# OBDII-Ist.net
KiCad netlist of a schematic drawn in Altium Designer
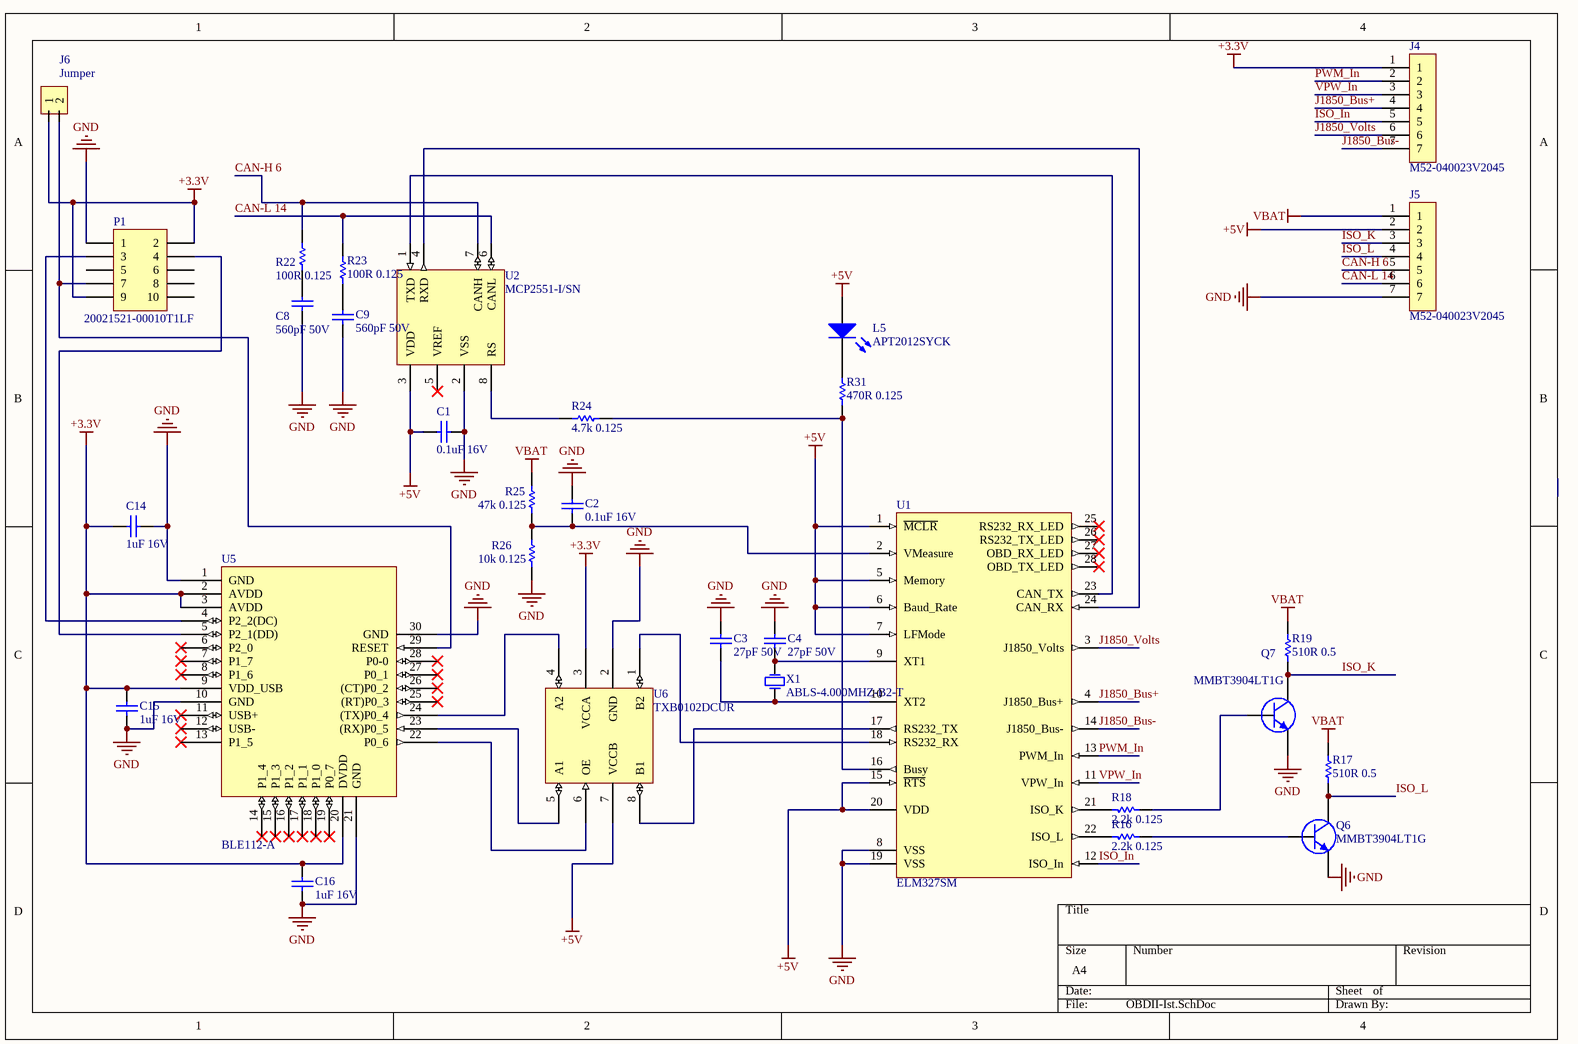
[diagram p0: OBDII-Ist.SchDoc]

(export (version "E")
  (design (tool "Eeschema 10.0.6"))
  (components
    (comp (ref "C1")
      (value "0.1uF 16V")
      (footprint "1608[0603]")
      (description "Surface-Mount Ceramic Multilayer Capacitor, 0.1uF, X5R, 10% Tolerance, 0603 Size, 16V")
      (fields (field (name "PUBLISHER") "Altium Limited"))
      (libsource (lib "OBDII-components") (part "GRM188R61C104KA01D"))
    )
    (comp (ref "C2")
      (value "0.1uF 16V")
      (footprint "1608[0603]")
      (description "Surface-Mount Ceramic Multilayer Capacitor, 0.1uF, X5R, 10% Tolerance, 0603 Size, 16V")
      (fields (field (name "PUBLISHER") "Altium Limited"))
      (libsource (lib "OBDII-components") (part "GRM188R61C104KA01D"))
    )
    (comp (ref "C3")
      (value "27pF 50V")
      (footprint "1608[0603]")
      (description "Surface-Mount Ceramic Multilayer Capacitor, 27pF, 5% Tolerance, 0603 Size, 50V")
      (fields (field (name "PUBLISHER") "Altium Limited"))
      (libsource (lib "OBDII-components") (part "CC0603JRNPO9BN270"))
    )
    (comp (ref "C4")
      (value "27pF 50V")
      (footprint "1608[0603]")
      (description "Surface-Mount Ceramic Multilayer Capacitor, 27pF, 5% Tolerance, 0603 Size, 50V")
      (fields (field (name "PUBLISHER") "Altium Limited"))
      (libsource (lib "OBDII-components") (part "CC0603JRNPO9BN270"))
    )
    (comp (ref "C8")
      (value "560pF 50V")
      (footprint "0402")
      (description "Surface-Mount Ceramic Multilayer Capacitor, 560pF, 5% Tolerance, 0402 Size, 50V")
      (fields (field (name "PUBLISHER") "Altium Limited"))
      (libsource (lib "OBDII-components") (part "C0402C561J5GACTU"))
    )
    (comp (ref "C9")
      (value "560pF 50V")
      (footprint "0402")
      (description "Surface-Mount Ceramic Multilayer Capacitor, 560pF, 5% Tolerance, 0402 Size, 50V")
      (fields (field (name "PUBLISHER") "Altium Limited"))
      (libsource (lib "OBDII-components") (part "C0402C561J5GACTU"))
    )
    (comp (ref "C14")
      (value "1uF 16V")
      (footprint "1608[0603]")
      (description "Surface-Mount Ceramic Multilayer Capacitor, 1uF, X7R, 10% Tolerance, 0603 Size, 16V")
      (libsource (lib "OBDII-components") (part "C1608X7R1C105K080AC"))
    )
    (comp (ref "C15")
      (value "1uF 16V")
      (footprint "1608[0603]")
      (description "Surface-Mount Ceramic Multilayer Capacitor, 1uF, X7R, 10% Tolerance, 0603 Size, 16V")
      (libsource (lib "OBDII-components") (part "C1608X7R1C105K080AC"))
    )
    (comp (ref "C16")
      (value "1uF 16V")
      (footprint "1608[0603]")
      (description "Surface-Mount Ceramic Multilayer Capacitor, 1uF, X7R, 10% Tolerance, 0603 Size, 16V")
      (libsource (lib "OBDII-components") (part "C1608X7R1C105K080AC"))
    )
    (comp (ref "J4")
      (value "M52-040023V2045")
      (footprint "M52-040023V2045_hols")
      (description "CONN HEADER .050\" 50POS PCB GOLD")
      (fields (field (name "MANUFACTURER") "Harwin"))
      (libsource (lib "OBDII-components") (part "M52-040023V2045_hols"))
    )
    (comp (ref "J5")
      (value "M52-040023V2045")
      (footprint "M52-040023V2045_hols")
      (description "CONN HEADER .050\" 50POS PCB GOLD")
      (fields (field (name "MANUFACTURER") "Harwin"))
      (libsource (lib "OBDII-components") (part "M52-040023V2045_hols"))
    )
    (comp (ref "J6")
      (value "Jumper")
      (footprint "Jumper")
      (description "Solder Jumper")
      (libsource (lib "OBDII-components") (part "Jumper"))
    )
    (comp (ref "L5")
      (value "APT2012SYCK")
      (footprint "LED-0805")
      (description "Typical BLUE SiC LED")
      (libsource (lib "OBDII-components") (part "APT2012SYCK"))
    )
    (comp (ref "P1")
      (value "20021521-00010T1LF")
      (footprint "20021521-00010T1LF")
      (description "Header, 5-Pin, Dual row,SMT SHOULDED")
      (fields (field (name "TYPE") "20021521-00010T1LF") (field (name "PUBLISHER") "Altium Limited"))
      (libsource (lib "OBDII-components") (part "20021521-00010T1LF"))
    )
    (comp (ref "Q6")
      (value "MMBT3904LT1G")
      (footprint "SOT23")
      (description "NPN 3904 General Purpose Amplifier")
      (fields
        (field (name "MANUFACTURER") "ON Semiconductor")
        (field (name "PUBLISHER") "Vanteon")
        (field (name "APPROVED") "Yes by Implemenation")
      )
      (libsource (lib "OBDII-components") (part "MMBT3904LT1G"))
    )
    (comp (ref "Q7")
      (value "MMBT3904LT1G")
      (footprint "SOT23")
      (description "NPN 3904 General Purpose Amplifier")
      (fields
        (field (name "MANUFACTURER") "ON Semiconductor")
        (field (name "PUBLISHER") "Vanteon")
        (field (name "APPROVED") "Yes by Implemenation")
      )
      (libsource (lib "OBDII-components") (part "MMBT3904LT1G"))
    )
    (comp (ref "R16")
      (value "2.2k 0.125")
      (footprint "ERA-0805")
      (description "Rectangular Thick Film Chip Resistor, 2.2 kOhm, 0.1% Tolerance, 0805 Size, 0.125 W")
      (libsource (lib "OBDII-components") (part "ERA-6AEB222V"))
    )
    (comp (ref "R17")
      (value "510R 0.5")
      (footprint "ERJ-1210")
      (description "Rectangular Thick Film Chip Resistor, 510 Ohm, 1% Tolerance, 1210 Size, 0.5 W")
      (libsource (lib "OBDII-components") (part "ERJ-14NF5100U"))
    )
    (comp (ref "R18")
      (value "2.2k 0.125")
      (footprint "ERA-0805")
      (description "Rectangular Thick Film Chip Resistor, 2.2 kOhm, 0.1% Tolerance, 0805 Size, 0.125 W")
      (libsource (lib "OBDII-components") (part "ERA-6AEB222V"))
    )
    (comp (ref "R19")
      (value "510R 0.5")
      (footprint "ERJ-1210")
      (description "Rectangular Thick Film Chip Resistor, 510 Ohm, 1% Tolerance, 1210 Size, 0.5 W")
      (libsource (lib "OBDII-components") (part "ERJ-14NF5100U"))
    )
    (comp (ref "R22")
      (value "100R 0.125")
      (footprint "ERA-0805")
      (description "Rectangular Thick Film Chip Resistor, 100 Ohm, 0.1% Tolerance, 0805 Size, 0.125 W")
      (libsource (lib "OBDII-components") (part "ERA-6AEB101V"))
    )
    (comp (ref "R23")
      (value "100R 0.125")
      (footprint "ERA-0805")
      (description "Rectangular Thick Film Chip Resistor, 100 Ohm, 0.1% Tolerance, 0805 Size, 0.125 W")
      (libsource (lib "OBDII-components") (part "ERA-6AEB101V"))
    )
    (comp (ref "R24")
      (value "4.7k 0.125")
      (footprint "ERA-0805")
      (description "Rectangular Thick Film Chip Resistor, 4.7 kOhm, 0.1% Tolerance, 0805 Size, 0.125 W")
      (libsource (lib "OBDII-components") (part "ERA-6AEB472V"))
    )
    (comp (ref "R25")
      (value "47k 0.125")
      (footprint "ERA-0805")
      (description "Rectangular Thick Film Chip Resistor, 47 kOhm, 0.1% Tolerance, 0805 Size, 0.125 W")
      (libsource (lib "OBDII-components") (part "ERA-6AEB473V"))
    )
    (comp (ref "R26")
      (value "10k 0.125")
      (footprint "ERA-0805")
      (description "Rectangular Thick Film Chip Resistor, 10 kOhm, 0.1% Tolerance, 0805 Size, 0.125 W")
      (libsource (lib "OBDII-components") (part "ERA-6AEB103V"))
    )
    (comp (ref "R31")
      (value "470R 0.125")
      (footprint "ERA-0805")
      (description "Rectangular Thick Film Chip Resistor, 470 Ohm, 0.1% Tolerance, 0805 Size, 0.125 W")
      (libsource (lib "OBDII-components") (part "ERA-6AEB471V"))
    )
    (comp (ref "U1")
      (value "ELM327SM")
      (footprint "SOIC-28N")
      (description "OBDII Interpreter IC")
      (fields (field (name "MANUFACTURER") "Elm Electronics"))
      (libsource (lib "OBDII-components") (part "ELM327_SOIC"))
    )
    (comp (ref "U2")
      (value "MCP2551-I/SN")
      (footprint "SOIC8N")
      (description "IC TRANSCEIVER CAN HI-SPD 8-SOIC")
      (fields (field (name "MANUFACTURER") "Microchip Technology"))
      (libsource (lib "OBDII-components") (part "MCP2551-I/SN"))
    )
    (comp (ref "U5")
      (value "BLE112-A")
      (footprint "BLE112-A - II")
      (description "BLE112 Bluetooth Smart Module")
      (libsource (lib "OBDII-components") (part "BLE112-A"))
    )
    (comp (ref "U6")
      (value "TXB0102DCUR")
      (footprint "TXB0102DCUR")
      (description "2-Bit Bidirectional Voltage-Level Translator with Auto Direction Sensing and +/-15-kV ESD Protect")
      (libsource (lib "OBDII-components") (part "TXB0102DCUR"))
    )
    (comp (ref "X1")
      (value "ABLS-4.000MHZ-B2-T")
      (footprint "HC-49/US")
      (description "CRYSTAL 4.000 MHZ 18PF SMD")
      (fields (field (name "MANUFACTURER") "Abracon"))
      (libsource (lib "OBDII-components") (part "ABLS-4.000MHZ-B2-T"))
    )
  )
  (nets
    (net (code "1") (name "+3.3V") (class "Default")
      (node (ref "C14") (pin "1") (pinfunction "1_1") (pintype "passive"))
      (node (ref "C15") (pin "2") (pinfunction "2_2") (pintype "passive"))
      (node (ref "C16") (pin "2") (pinfunction "2_2") (pintype "passive"))
      (node (ref "J4") (pin "1") (pinfunction "1_1") (pintype "passive"))
      (node (ref "J6") (pin "1") (pinfunction "1_1") (pintype "passive"))
      (node (ref "P1") (pin "2") (pinfunction "2_2") (pintype "passive"))
      (node (ref "P1") (pin "9") (pinfunction "9_9") (pintype "passive"))
      (node (ref "U5") (pin "2") (pinfunction "AVDD_2") (pintype "power_in"))
      (node (ref "U5") (pin "20") (pinfunction "DVDD_20") (pintype "power_in"))
      (node (ref "U5") (pin "3") (pinfunction "AVDD_3") (pintype "power_in"))
      (node (ref "U5") (pin "9") (pinfunction "VDD_USB_9") (pintype "power_in"))
      (node (ref "U6") (pin "3") (pinfunction "VCCA_3") (pintype "power_in"))
    )
    (net (code "2") (name "+5V") (class "Default")
      (node (ref "C1") (pin "1") (pinfunction "1_1") (pintype "passive"))
      (node (ref "J5") (pin "2") (pinfunction "2_2") (pintype "passive"))
      (node (ref "L5") (pin "1") (pinfunction "A_1") (pintype "passive"))
      (node (ref "U1") (pin "1") (pinfunction "~{MCLR}_1") (pintype "input"))
      (node (ref "U1") (pin "15") (pinfunction "~{RTS}_15") (pintype "input"))
      (node (ref "U1") (pin "20") (pinfunction "VDD_20") (pintype "power_in"))
      (node (ref "U1") (pin "5") (pinfunction "Memory_5") (pintype "input"))
      (node (ref "U1") (pin "6") (pinfunction "Baud_Rate_6") (pintype "input"))
      (node (ref "U1") (pin "7") (pinfunction "LFMode_7") (pintype "input"))
      (node (ref "U2") (pin "3") (pinfunction "VDD_3") (pintype "power_in"))
      (node (ref "U6") (pin "7") (pinfunction "VCCB_7") (pintype "power_in"))
    )
    (net (code "3") (name "/CAN-H 6") (class "Default")
      (node (ref "J5") (pin "5") (pinfunction "5_5") (pintype "passive"))
      (node (ref "R22") (pin "2") (pinfunction "2_2") (pintype "passive"))
      (node (ref "U2") (pin "7") (pinfunction "CANH_7") (pintype "bidirectional"))
    )
    (net (code "4") (name "/CAN-L 14") (class "Default")
      (node (ref "J5") (pin "6") (pinfunction "6_6") (pintype "passive"))
      (node (ref "R23") (pin "2") (pinfunction "2_2") (pintype "passive"))
      (node (ref "U2") (pin "6") (pinfunction "CANL_6") (pintype "bidirectional"))
    )
    (net (code "5") (name "/ISO_In") (class "Default")
      (node (ref "J4") (pin "5") (pinfunction "5_5") (pintype "passive"))
      (node (ref "U1") (pin "12") (pinfunction "ISO_In_12") (pintype "input"))
    )
    (net (code "6") (name "/ISO_K") (class "Default")
      (node (ref "J5") (pin "3") (pinfunction "3_3") (pintype "passive"))
      (node (ref "Q7") (pin "3") (pinfunction "C_3") (pintype "passive"))
      (node (ref "R19") (pin "1") (pinfunction "1_1") (pintype "passive"))
    )
    (net (code "7") (name "/ISO_L") (class "Default")
      (node (ref "J5") (pin "4") (pinfunction "4_4") (pintype "passive"))
      (node (ref "Q6") (pin "3") (pinfunction "C_3") (pintype "passive"))
      (node (ref "R17") (pin "1") (pinfunction "1_1") (pintype "passive"))
    )
    (net (code "8") (name "/J1850_Bus+") (class "Default")
      (node (ref "J4") (pin "4") (pinfunction "4_4") (pintype "passive"))
      (node (ref "U1") (pin "4") (pinfunction "J1850_Bus+_4") (pintype "output"))
    )
    (net (code "9") (name "/J1850_Bus-") (class "Default")
      (node (ref "J4") (pin "7") (pinfunction "7_7") (pintype "passive"))
      (node (ref "U1") (pin "14") (pinfunction "J1850_Bus-_14") (pintype "output"))
    )
    (net (code "10") (name "/J1850_Volts") (class "Default")
      (node (ref "J4") (pin "6") (pinfunction "6_6") (pintype "passive"))
      (node (ref "U1") (pin "3") (pinfunction "J1850_Volts_3") (pintype "output"))
    )
    (net (code "11") (name "/PWM_In") (class "Default")
      (node (ref "J4") (pin "2") (pinfunction "2_2") (pintype "passive"))
      (node (ref "U1") (pin "13") (pinfunction "PWM_In_13") (pintype "input"))
    )
    (net (code "12") (name "/VPW_In") (class "Default")
      (node (ref "J4") (pin "3") (pinfunction "3_3") (pintype "passive"))
      (node (ref "U1") (pin "11") (pinfunction "VPW_In_11") (pintype "input"))
    )
    (net (code "13") (name "GND") (class "Default")
      (node (ref "C1") (pin "2") (pinfunction "2_2") (pintype "passive"))
      (node (ref "C14") (pin "2") (pinfunction "2_2") (pintype "passive"))
      (node (ref "C15") (pin "1") (pinfunction "1_1") (pintype "passive"))
      (node (ref "C16") (pin "1") (pinfunction "1_1") (pintype "passive"))
      (node (ref "C2") (pin "2") (pinfunction "2_2") (pintype "passive"))
      (node (ref "C3") (pin "2") (pinfunction "2_2") (pintype "passive"))
      (node (ref "C4") (pin "2") (pinfunction "2_2") (pintype "passive"))
      (node (ref "C8") (pin "1") (pinfunction "1_1") (pintype "passive"))
      (node (ref "C9") (pin "1") (pinfunction "1_1") (pintype "passive"))
      (node (ref "J5") (pin "7") (pinfunction "7_7") (pintype "passive"))
      (node (ref "P1") (pin "1") (pinfunction "1_1") (pintype "passive"))
      (node (ref "Q6") (pin "2") (pinfunction "E_2") (pintype "passive"))
      (node (ref "Q7") (pin "2") (pinfunction "E_2") (pintype "passive"))
      (node (ref "R26") (pin "1") (pinfunction "1_1") (pintype "passive"))
      (node (ref "U1") (pin "19") (pinfunction "VSS_19") (pintype "power_in"))
      (node (ref "U1") (pin "8") (pinfunction "VSS_8") (pintype "power_in"))
      (node (ref "U2") (pin "2") (pinfunction "VSS_2") (pintype "power_in"))
      (node (ref "U5") (pin "1") (pinfunction "GND_1") (pintype "power_in"))
      (node (ref "U5") (pin "10") (pinfunction "GND_10") (pintype "passive"))
      (node (ref "U5") (pin "21") (pinfunction "GND_21") (pintype "power_in"))
      (node (ref "U5") (pin "30") (pinfunction "GND_30") (pintype "power_in"))
      (node (ref "U6") (pin "2") (pinfunction "GND_2") (pintype "power_in"))
    )
    (net (code "14") (name "Net-(C8-Pad2)") (class "Default")
      (node (ref "C8") (pin "2") (pinfunction "2_2") (pintype "passive"))
      (node (ref "R22") (pin "1") (pinfunction "1_1") (pintype "passive"))
    )
    (net (code "15") (name "Net-(C9-Pad2)") (class "Default")
      (node (ref "C9") (pin "2") (pinfunction "2_2") (pintype "passive"))
      (node (ref "R23") (pin "1") (pinfunction "1_1") (pintype "passive"))
    )
    (net (code "16") (name "Net-(L5-K)") (class "Default")
      (node (ref "L5") (pin "2") (pinfunction "K_2") (pintype "passive"))
      (node (ref "R31") (pin "2") (pinfunction "2_2") (pintype "passive"))
    )
    (net (code "17") (name "Net-(Q6-B)") (class "Default")
      (node (ref "Q6") (pin "1") (pinfunction "B_1") (pintype "passive"))
      (node (ref "R16") (pin "1") (pinfunction "1_1") (pintype "passive"))
    )
    (net (code "18") (name "Net-(Q7-B)") (class "Default")
      (node (ref "Q7") (pin "1") (pinfunction "B_1") (pintype "passive"))
      (node (ref "R18") (pin "1") (pinfunction "1_1") (pintype "passive"))
    )
    (net (code "19") (name "Net-(U1-Busy)") (class "Default")
      (node (ref "R24") (pin "2") (pinfunction "2_2") (pintype "passive"))
      (node (ref "R31") (pin "1") (pinfunction "1_1") (pintype "passive"))
      (node (ref "U1") (pin "16") (pinfunction "Busy_16") (pintype "output"))
    )
    (net (code "20") (name "Net-(U1-CAN_RX)") (class "Default")
      (node (ref "U1") (pin "24") (pinfunction "CAN_RX_24") (pintype "input"))
      (node (ref "U2") (pin "4") (pinfunction "RXD_4") (pintype "output"))
    )
    (net (code "21") (name "Net-(U1-CAN_TX)") (class "Default")
      (node (ref "U1") (pin "23") (pinfunction "CAN_TX_23") (pintype "output"))
      (node (ref "U2") (pin "1") (pinfunction "TXD_1") (pintype "input"))
    )
    (net (code "22") (name "Net-(U1-ISO_K)") (class "Default")
      (node (ref "R18") (pin "2") (pinfunction "2_2") (pintype "passive"))
      (node (ref "U1") (pin "21") (pinfunction "ISO_K_21") (pintype "output"))
    )
    (net (code "23") (name "Net-(U1-ISO_L)") (class "Default")
      (node (ref "R16") (pin "2") (pinfunction "2_2") (pintype "passive"))
      (node (ref "U1") (pin "22") (pinfunction "ISO_L_22") (pintype "output"))
    )
    (net (code "24") (name "Net-(U1-RS232_RX)") (class "Default")
      (node (ref "U1") (pin "18") (pinfunction "RS232_RX_18") (pintype "input"))
      (node (ref "U6") (pin "1") (pinfunction "B2_1") (pintype "bidirectional"))
    )
    (net (code "25") (name "Net-(U1-RS232_TX)") (class "Default")
      (node (ref "U1") (pin "17") (pinfunction "RS232_TX_17") (pintype "output"))
      (node (ref "U6") (pin "8") (pinfunction "B1_8") (pintype "bidirectional"))
    )
    (net (code "26") (name "Net-(U1-VMeasure)") (class "Default")
      (node (ref "C2") (pin "1") (pinfunction "1_1") (pintype "passive"))
      (node (ref "R25") (pin "1") (pinfunction "1_1") (pintype "passive"))
      (node (ref "R26") (pin "2") (pinfunction "2_2") (pintype "passive"))
      (node (ref "U1") (pin "2") (pinfunction "VMeasure_2") (pintype "input"))
    )
    (net (code "27") (name "Net-(U1-XT1)") (class "Default")
      (node (ref "C4") (pin "1") (pinfunction "1_1") (pintype "passive"))
      (node (ref "U1") (pin "9") (pinfunction "XT1_9") (pintype "passive"))
      (node (ref "X1") (pin "2") (pinfunction "OSC2_2") (pintype "passive"))
    )
    (net (code "28") (name "Net-(U1-XT2)") (class "Default")
      (node (ref "C3") (pin "1") (pinfunction "1_1") (pintype "passive"))
      (node (ref "U1") (pin "10") (pinfunction "XT2_10") (pintype "passive"))
      (node (ref "X1") (pin "1") (pinfunction "OSC1_1") (pintype "passive"))
    )
    (net (code "29") (name "Net-(U2-RS)") (class "Default")
      (node (ref "R24") (pin "1") (pinfunction "1_1") (pintype "passive"))
      (node (ref "U2") (pin "8") (pinfunction "RS_8") (pintype "passive"))
    )
    (net (code "30") (name "Net-(U5-(RX)P0_5)") (class "Default")
      (node (ref "U5") (pin "23") (pinfunction "(RX)P0_5_23") (pintype "input"))
      (node (ref "U6") (pin "5") (pinfunction "A1_5") (pintype "bidirectional"))
    )
    (net (code "31") (name "Net-(U5-(TX)P0_4)") (class "Default")
      (node (ref "U5") (pin "24") (pinfunction "(TX)P0_4_24") (pintype "output"))
      (node (ref "U6") (pin "4") (pinfunction "A2_4") (pintype "bidirectional"))
    )
    (net (code "32") (name "Net-(U5-P0_6)") (class "Default")
      (node (ref "U5") (pin "22") (pinfunction "P0_6_22") (pintype "output"))
      (node (ref "U6") (pin "6") (pinfunction "OE_6") (pintype "input"))
    )
    (net (code "33") (name "Net-(U5-P2_1(DD))") (class "Default")
      (node (ref "P1") (pin "4") (pinfunction "4_4") (pintype "passive"))
      (node (ref "U5") (pin "5") (pinfunction "P2_1(DD)_5") (pintype "bidirectional"))
    )
    (net (code "34") (name "Net-(U5-P2_2(DC))") (class "Default")
      (node (ref "P1") (pin "3") (pinfunction "3_3") (pintype "passive"))
      (node (ref "U5") (pin "4") (pinfunction "P2_2(DC)_4") (pintype "bidirectional"))
    )
    (net (code "35") (name "Net-(U5-RESET)") (class "Default")
      (node (ref "J6") (pin "2") (pinfunction "2_2") (pintype "passive"))
      (node (ref "P1") (pin "7") (pinfunction "7_7") (pintype "passive"))
      (node (ref "U5") (pin "29") (pinfunction "RESET_29") (pintype "input"))
    )
    (net (code "36") (name "VBAT") (class "Default")
      (node (ref "J5") (pin "1") (pinfunction "1_1") (pintype "passive"))
      (node (ref "R17") (pin "2") (pinfunction "2_2") (pintype "passive"))
      (node (ref "R19") (pin "2") (pinfunction "2_2") (pintype "passive"))
      (node (ref "R25") (pin "2") (pinfunction "2_2") (pintype "passive"))
    )
    (net (code "37") (name "unconnected-(P1-Pad5)") (class "Default")
      (node (ref "P1") (pin "5") (pinfunction "5_5") (pintype "passive"))
    )
    (net (code "38") (name "unconnected-(P1-Pad6)") (class "Default")
      (node (ref "P1") (pin "6") (pinfunction "6_6") (pintype "passive"))
    )
    (net (code "39") (name "unconnected-(P1-Pad8)") (class "Default")
      (node (ref "P1") (pin "8") (pinfunction "8_8") (pintype "passive"))
    )
    (net (code "40") (name "unconnected-(P1-Pad10)") (class "Default")
      (node (ref "P1") (pin "10") (pinfunction "10_10") (pintype "passive"))
    )
    (net (code "41") (name "unconnected-(U1-OBD_RX_LED-Pad27)") (class "Default")
      (node (ref "U1") (pin "27") (pinfunction "OBD_RX_LED_27") (pintype "output+no_connect"))
    )
    (net (code "42") (name "unconnected-(U1-OBD_TX_LED-Pad28)") (class "Default")
      (node (ref "U1") (pin "28") (pinfunction "OBD_TX_LED_28") (pintype "output+no_connect"))
    )
    (net (code "43") (name "unconnected-(U1-RS232_RX_LED-Pad25)") (class "Default")
      (node (ref "U1") (pin "25") (pinfunction "RS232_RX_LED_25") (pintype "output+no_connect"))
    )
    (net (code "44") (name "unconnected-(U1-RS232_TX_LED-Pad26)") (class "Default")
      (node (ref "U1") (pin "26") (pinfunction "RS232_TX_LED_26") (pintype "output+no_connect"))
    )
    (net (code "45") (name "unconnected-(U2-VREF-Pad5)") (class "Default")
      (node (ref "U2") (pin "5") (pinfunction "VREF_5") (pintype "passive+no_connect"))
    )
    (net (code "46") (name "unconnected-(U5-(CT)P0_2-Pad26)") (class "Default")
      (node (ref "U5") (pin "26") (pinfunction "(CT)P0_2_26") (pintype "bidirectional+no_connect"))
    )
    (net (code "47") (name "unconnected-(U5-(RT)P0_3-Pad25)") (class "Default")
      (node (ref "U5") (pin "25") (pinfunction "(RT)P0_3_25") (pintype "bidirectional+no_connect"))
    )
    (net (code "48") (name "unconnected-(U5-P0-0-Pad28)") (class "Default")
      (node (ref "U5") (pin "28") (pinfunction "P0-0_28") (pintype "bidirectional+no_connect"))
    )
    (net (code "49") (name "unconnected-(U5-P0_1-Pad27)") (class "Default")
      (node (ref "U5") (pin "27") (pinfunction "P0_1_27") (pintype "bidirectional+no_connect"))
    )
    (net (code "50") (name "unconnected-(U5-P0_7-Pad19)") (class "Default")
      (node (ref "U5") (pin "19") (pinfunction "P0_7_19") (pintype "bidirectional+no_connect"))
    )
    (net (code "51") (name "unconnected-(U5-P1_0-Pad18)") (class "Default")
      (node (ref "U5") (pin "18") (pinfunction "P1_0_18") (pintype "bidirectional+no_connect"))
    )
    (net (code "52") (name "unconnected-(U5-P1_1-Pad17)") (class "Default")
      (node (ref "U5") (pin "17") (pinfunction "P1_1_17") (pintype "bidirectional+no_connect"))
    )
    (net (code "53") (name "unconnected-(U5-P1_2-Pad16)") (class "Default")
      (node (ref "U5") (pin "16") (pinfunction "P1_2_16") (pintype "bidirectional+no_connect"))
    )
    (net (code "54") (name "unconnected-(U5-P1_3-Pad15)") (class "Default")
      (node (ref "U5") (pin "15") (pinfunction "P1_3_15") (pintype "bidirectional+no_connect"))
    )
    (net (code "55") (name "unconnected-(U5-P1_4-Pad14)") (class "Default")
      (node (ref "U5") (pin "14") (pinfunction "P1_4_14") (pintype "bidirectional+no_connect"))
    )
    (net (code "56") (name "unconnected-(U5-P1_5-Pad13)") (class "Default")
      (node (ref "U5") (pin "13") (pinfunction "P1_5_13") (pintype "passive+no_connect"))
    )
    (net (code "57") (name "unconnected-(U5-P1_6-Pad8)") (class "Default")
      (node (ref "U5") (pin "8") (pinfunction "P1_6_8") (pintype "bidirectional+no_connect"))
    )
    (net (code "58") (name "unconnected-(U5-P1_7-Pad7)") (class "Default")
      (node (ref "U5") (pin "7") (pinfunction "P1_7_7") (pintype "bidirectional+no_connect"))
    )
    (net (code "59") (name "unconnected-(U5-P2_0-Pad6)") (class "Default")
      (node (ref "U5") (pin "6") (pinfunction "P2_0_6") (pintype "bidirectional+no_connect"))
    )
    (net (code "60") (name "unconnected-(U5-USB+-Pad11)") (class "Default")
      (node (ref "U5") (pin "11") (pinfunction "USB+_11") (pintype "bidirectional+no_connect"))
    )
    (net (code "61") (name "unconnected-(U5-USB--Pad12)") (class "Default")
      (node (ref "U5") (pin "12") (pinfunction "USB-_12") (pintype "bidirectional+no_connect"))
    )
  )
)
